# adc.net
KiCad netlist of a schematic drawn in Altium Designer
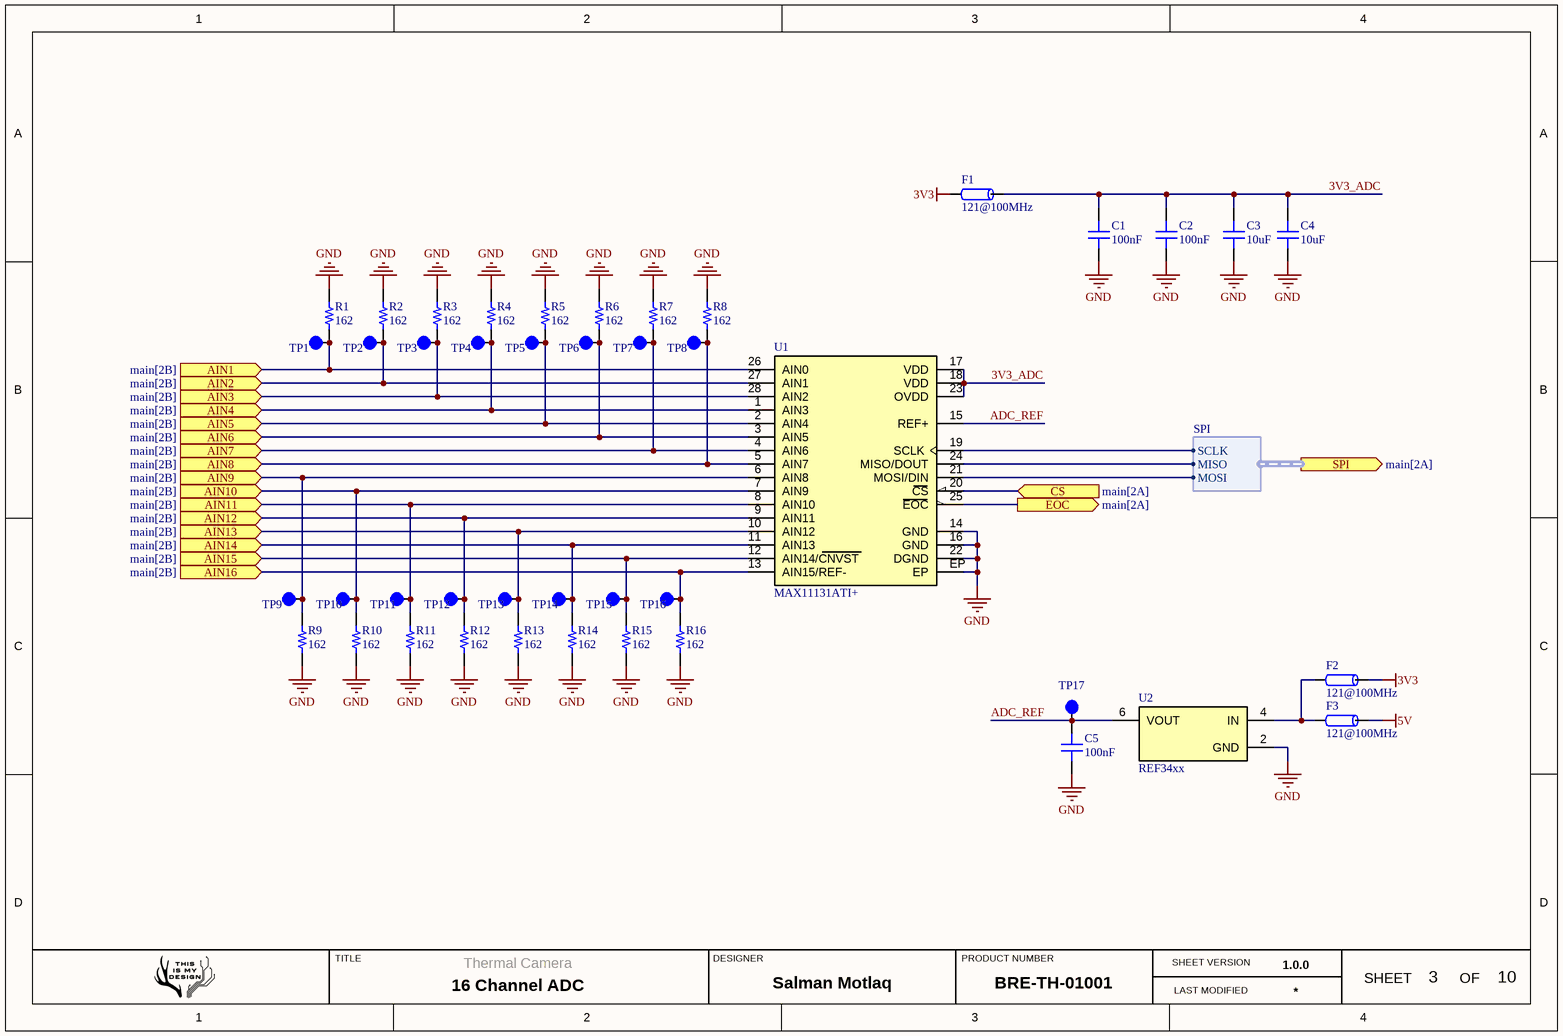
[diagram p0: adc.SchDoc]

(export (version "E")
  (design (tool "Eeschema 10.0.6"))
  (components
    (comp (ref "C1")
      (value "100nF")
      (footprint "CAP 0603_1608")
      (description "SMT Capacitor")
      (libsource (lib "Capacitor") (part "Cap 0603"))
    )
    (comp (ref "C2")
      (value "100nF")
      (footprint "CAP 0603_1608")
      (description "SMT Capacitor")
      (libsource (lib "Capacitor") (part "Cap 0603"))
    )
    (comp (ref "C3")
      (value "10uF")
      (footprint "CAP 0603_1608")
      (description "SMT Capacitor")
      (libsource (lib "Capacitor") (part "Cap 0603"))
    )
    (comp (ref "C4")
      (value "10uF")
      (footprint "CAP 0603_1608")
      (description "SMT Capacitor")
      (libsource (lib "Capacitor") (part "Cap 0603"))
    )
    (comp (ref "C5")
      (value "100nF")
      (footprint "CAP 0603_1608")
      (description "SMT Capacitor")
      (libsource (lib "Capacitor") (part "Cap 0603"))
    )
    (comp (ref "F1")
      (value "121@100MHz")
      (footprint "Ferrite-0805")
      (description "Ferrite Bead")
      (libsource (lib "Salman_lib") (part "Ferrite Bead"))
    )
    (comp (ref "F2")
      (value "121@100MHz")
      (footprint "Ferrite-0805")
      (description "Ferrite Bead")
      (libsource (lib "Salman_lib") (part "Ferrite Bead"))
    )
    (comp (ref "F3")
      (value "121@100MHz")
      (footprint "Ferrite-0805")
      (description "Ferrite Bead")
      (libsource (lib "Salman_lib") (part "Ferrite Bead"))
    )
    (comp (ref "R1")
      (value "162")
      (footprint "RES 0402_1005")
      (description "SMT Resistor")
      (libsource (lib "Resistor") (part "Res 0402"))
    )
    (comp (ref "R2")
      (value "162")
      (footprint "RES 0402_1005")
      (description "SMT Resistor")
      (libsource (lib "Resistor") (part "Res 0402"))
    )
    (comp (ref "R3")
      (value "162")
      (footprint "RES 0402_1005")
      (description "SMT Resistor")
      (libsource (lib "Resistor") (part "Res 0402"))
    )
    (comp (ref "R4")
      (value "162")
      (footprint "RES 0402_1005")
      (description "SMT Resistor")
      (libsource (lib "Resistor") (part "Res 0402"))
    )
    (comp (ref "R5")
      (value "162")
      (footprint "RES 0402_1005")
      (description "SMT Resistor")
      (libsource (lib "Resistor") (part "Res 0402"))
    )
    (comp (ref "R6")
      (value "162")
      (footprint "RES 0402_1005")
      (description "SMT Resistor")
      (libsource (lib "Resistor") (part "Res 0402"))
    )
    (comp (ref "R7")
      (value "162")
      (footprint "RES 0402_1005")
      (description "SMT Resistor")
      (libsource (lib "Resistor") (part "Res 0402"))
    )
    (comp (ref "R8")
      (value "162")
      (footprint "RES 0402_1005")
      (description "SMT Resistor")
      (libsource (lib "Resistor") (part "Res 0402"))
    )
    (comp (ref "R9")
      (value "162")
      (footprint "RES 0402_1005")
      (description "SMT Resistor")
      (libsource (lib "Resistor") (part "Res 0402"))
    )
    (comp (ref "R10")
      (value "162")
      (footprint "RES 0402_1005")
      (description "SMT Resistor")
      (libsource (lib "Resistor") (part "Res 0402"))
    )
    (comp (ref "R11")
      (value "162")
      (footprint "RES 0402_1005")
      (description "SMT Resistor")
      (libsource (lib "Resistor") (part "Res 0402"))
    )
    (comp (ref "R12")
      (value "162")
      (footprint "RES 0402_1005")
      (description "SMT Resistor")
      (libsource (lib "Resistor") (part "Res 0402"))
    )
    (comp (ref "R13")
      (value "162")
      (footprint "RES 0402_1005")
      (description "SMT Resistor")
      (libsource (lib "Resistor") (part "Res 0402"))
    )
    (comp (ref "R14")
      (value "162")
      (footprint "RES 0402_1005")
      (description "SMT Resistor")
      (libsource (lib "Resistor") (part "Res 0402"))
    )
    (comp (ref "R15")
      (value "162")
      (footprint "RES 0402_1005")
      (description "SMT Resistor")
      (libsource (lib "Resistor") (part "Res 0402"))
    )
    (comp (ref "R16")
      (value "162")
      (footprint "RES 0402_1005")
      (description "SMT Resistor")
      (libsource (lib "Resistor") (part "Res 0402"))
    )
    (comp (ref "TP1")
      (value "Test Point")
      (footprint "TEST_POINT_0R5")
      (description "PCB Test Point")
      (libsource (lib "BayanLib") (part "Test Point"))
    )
    (comp (ref "TP2")
      (value "Test Point")
      (footprint "TEST_POINT_0R5")
      (description "PCB Test Point")
      (libsource (lib "BayanLib") (part "Test Point"))
    )
    (comp (ref "TP3")
      (value "Test Point")
      (footprint "TEST_POINT_0R5")
      (description "PCB Test Point")
      (libsource (lib "BayanLib") (part "Test Point"))
    )
    (comp (ref "TP4")
      (value "Test Point")
      (footprint "TEST_POINT_0R5")
      (description "PCB Test Point")
      (libsource (lib "BayanLib") (part "Test Point"))
    )
    (comp (ref "TP5")
      (value "Test Point")
      (footprint "TEST_POINT_0R5")
      (description "PCB Test Point")
      (libsource (lib "BayanLib") (part "Test Point"))
    )
    (comp (ref "TP6")
      (value "Test Point")
      (footprint "TEST_POINT_0R5")
      (description "PCB Test Point")
      (libsource (lib "BayanLib") (part "Test Point"))
    )
    (comp (ref "TP7")
      (value "Test Point")
      (footprint "TEST_POINT_0R5")
      (description "PCB Test Point")
      (libsource (lib "BayanLib") (part "Test Point"))
    )
    (comp (ref "TP8")
      (value "Test Point")
      (footprint "TEST_POINT_0R5")
      (description "PCB Test Point")
      (libsource (lib "BayanLib") (part "Test Point"))
    )
    (comp (ref "TP9")
      (value "Test Point")
      (footprint "TEST_POINT_0R5")
      (description "PCB Test Point")
      (libsource (lib "BayanLib") (part "Test Point"))
    )
    (comp (ref "TP10")
      (value "Test Point")
      (footprint "TEST_POINT_0R5")
      (description "PCB Test Point")
      (libsource (lib "BayanLib") (part "Test Point"))
    )
    (comp (ref "TP11")
      (value "Test Point")
      (footprint "TEST_POINT_0R5")
      (description "PCB Test Point")
      (libsource (lib "BayanLib") (part "Test Point"))
    )
    (comp (ref "TP12")
      (value "Test Point")
      (footprint "TEST_POINT_0R5")
      (description "PCB Test Point")
      (libsource (lib "BayanLib") (part "Test Point"))
    )
    (comp (ref "TP13")
      (value "Test Point")
      (footprint "TEST_POINT_0R5")
      (description "PCB Test Point")
      (libsource (lib "BayanLib") (part "Test Point"))
    )
    (comp (ref "TP14")
      (value "Test Point")
      (footprint "TEST_POINT_0R5")
      (description "PCB Test Point")
      (libsource (lib "BayanLib") (part "Test Point"))
    )
    (comp (ref "TP15")
      (value "Test Point")
      (footprint "TEST_POINT_0R5")
      (description "PCB Test Point")
      (libsource (lib "BayanLib") (part "Test Point"))
    )
    (comp (ref "TP16")
      (value "Test Point")
      (footprint "TEST_POINT_0R5")
      (description "PCB Test Point")
      (libsource (lib "BayanLib") (part "Test Point"))
    )
    (comp (ref "TP17")
      (value "Test Point")
      (footprint "TEST_POINT_0R5")
      (description "PCB Test Point")
      (libsource (lib "BayanLib") (part "Test Point"))
    )
    (comp (ref "U1")
      (value "MAX11131ATI+")
      (footprint "TQFN-28")
      (libsource (lib "Salman_lib") (part "MAX11131"))
    )
    (comp (ref "U2")
      (value "REF34xx")
      (footprint "SOT23-6L")
      (description "Voltage References low-drift, low-power")
      (libsource (lib "Salman_lib") (part "REF34xx"))
    )
  )
  (nets
    (net (code "2") (name "/3V3_ADC") (class "Default")
      (node (ref "C1") (pin "2") (pinfunction "2_2") (pintype "passive"))
      (node (ref "C2") (pin "2") (pinfunction "2_2") (pintype "passive"))
      (node (ref "C3") (pin "2") (pinfunction "2_2") (pintype "passive"))
      (node (ref "C4") (pin "2") (pinfunction "2_2") (pintype "passive"))
      (node (ref "F1") (pin "2") (pinfunction "66_2") (pintype "passive"))
      (node (ref "U1") (pin "17") (pinfunction "VDD_17") (pintype "passive"))
      (node (ref "U1") (pin "18") (pinfunction "VDD_18") (pintype "passive"))
      (node (ref "U1") (pin "23") (pinfunction "OVDD_23") (pintype "passive"))
    )
    (net (code "3") (name "/ADC_REF") (class "Default")
      (node (ref "C5") (pin "2") (pinfunction "2_2") (pintype "passive"))
      (node (ref "TP17") (pin "0") (pinfunction "0_0") (pintype "passive"))
      (node (ref "U1") (pin "15") (pinfunction "REF+_15") (pintype "passive"))
      (node (ref "U2") (pin "6") (pinfunction "VOUT_6") (pintype "passive"))
    )
    (net (code "4") (name "/AIN1") (class "Default")
      (node (ref "R1") (pin "1") (pinfunction "1_1") (pintype "passive"))
      (node (ref "TP1") (pin "0") (pinfunction "0_0") (pintype "passive"))
      (node (ref "U1") (pin "26") (pinfunction "AIN0_26") (pintype "passive"))
    )
    (net (code "5") (name "/AIN2") (class "Default")
      (node (ref "R2") (pin "1") (pinfunction "1_1") (pintype "passive"))
      (node (ref "TP2") (pin "0") (pinfunction "0_0") (pintype "passive"))
      (node (ref "U1") (pin "27") (pinfunction "AIN1_27") (pintype "passive"))
    )
    (net (code "6") (name "/AIN3") (class "Default")
      (node (ref "R3") (pin "1") (pinfunction "1_1") (pintype "passive"))
      (node (ref "TP3") (pin "0") (pinfunction "0_0") (pintype "passive"))
      (node (ref "U1") (pin "28") (pinfunction "AIN2_28") (pintype "passive"))
    )
    (net (code "7") (name "/AIN4") (class "Default")
      (node (ref "R4") (pin "1") (pinfunction "1_1") (pintype "passive"))
      (node (ref "TP4") (pin "0") (pinfunction "0_0") (pintype "passive"))
      (node (ref "U1") (pin "1") (pinfunction "AIN3_1") (pintype "passive"))
    )
    (net (code "8") (name "/AIN5") (class "Default")
      (node (ref "R5") (pin "1") (pinfunction "1_1") (pintype "passive"))
      (node (ref "TP5") (pin "0") (pinfunction "0_0") (pintype "passive"))
      (node (ref "U1") (pin "2") (pinfunction "AIN4_2") (pintype "passive"))
    )
    (net (code "9") (name "/AIN6") (class "Default")
      (node (ref "R6") (pin "1") (pinfunction "1_1") (pintype "passive"))
      (node (ref "TP6") (pin "0") (pinfunction "0_0") (pintype "passive"))
      (node (ref "U1") (pin "3") (pinfunction "AIN5_3") (pintype "passive"))
    )
    (net (code "10") (name "/AIN7") (class "Default")
      (node (ref "R7") (pin "1") (pinfunction "1_1") (pintype "passive"))
      (node (ref "TP7") (pin "0") (pinfunction "0_0") (pintype "passive"))
      (node (ref "U1") (pin "4") (pinfunction "AIN6_4") (pintype "passive"))
    )
    (net (code "11") (name "/AIN8") (class "Default")
      (node (ref "R8") (pin "1") (pinfunction "1_1") (pintype "passive"))
      (node (ref "TP8") (pin "0") (pinfunction "0_0") (pintype "passive"))
      (node (ref "U1") (pin "5") (pinfunction "AIN7_5") (pintype "passive"))
    )
    (net (code "12") (name "/AIN9") (class "Default")
      (node (ref "R9") (pin "2") (pinfunction "2_2") (pintype "passive"))
      (node (ref "TP9") (pin "0") (pinfunction "0_0") (pintype "passive"))
      (node (ref "U1") (pin "6") (pinfunction "AIN8_6") (pintype "passive"))
    )
    (net (code "13") (name "/AIN10") (class "Default")
      (node (ref "R10") (pin "2") (pinfunction "2_2") (pintype "passive"))
      (node (ref "TP10") (pin "0") (pinfunction "0_0") (pintype "passive"))
      (node (ref "U1") (pin "7") (pinfunction "AIN9_7") (pintype "passive"))
    )
    (net (code "14") (name "/AIN11") (class "Default")
      (node (ref "R11") (pin "2") (pinfunction "2_2") (pintype "passive"))
      (node (ref "TP11") (pin "0") (pinfunction "0_0") (pintype "passive"))
      (node (ref "U1") (pin "8") (pinfunction "AIN10_8") (pintype "passive"))
    )
    (net (code "15") (name "/AIN12") (class "Default")
      (node (ref "R12") (pin "2") (pinfunction "2_2") (pintype "passive"))
      (node (ref "TP12") (pin "0") (pinfunction "0_0") (pintype "passive"))
      (node (ref "U1") (pin "9") (pinfunction "AIN11_9") (pintype "passive"))
    )
    (net (code "16") (name "/AIN13") (class "Default")
      (node (ref "R13") (pin "2") (pinfunction "2_2") (pintype "passive"))
      (node (ref "TP13") (pin "0") (pinfunction "0_0") (pintype "passive"))
      (node (ref "U1") (pin "10") (pinfunction "AIN12_10") (pintype "passive"))
    )
    (net (code "17") (name "/AIN14") (class "Default")
      (node (ref "R14") (pin "2") (pinfunction "2_2") (pintype "passive"))
      (node (ref "TP14") (pin "0") (pinfunction "0_0") (pintype "passive"))
      (node (ref "U1") (pin "11") (pinfunction "AIN13_11") (pintype "passive"))
    )
    (net (code "18") (name "/AIN15") (class "Default")
      (node (ref "R15") (pin "2") (pinfunction "2_2") (pintype "passive"))
      (node (ref "TP15") (pin "0") (pinfunction "0_0") (pintype "passive"))
      (node (ref "U1") (pin "12") (pinfunction "AIN14/CNVST_12") (pintype "passive"))
    )
    (net (code "19") (name "/AIN16") (class "Default")
      (node (ref "R16") (pin "2") (pinfunction "2_2") (pintype "passive"))
      (node (ref "TP16") (pin "0") (pinfunction "0_0") (pintype "passive"))
      (node (ref "U1") (pin "13") (pinfunction "AIN15/REF-_13") (pintype "passive"))
    )
    (net (code "20") (name "/CS") (class "Default")
      (node (ref "U1") (pin "20") (pinfunction "CS_20") (pintype "passive"))
    )
    (net (code "21") (name "/EOC") (class "Default")
      (node (ref "U1") (pin "25") (pinfunction "EOC_25") (pintype "passive"))
    )
    (net (code "22") (name "/MISO") (class "Default")
      (node (ref "U1") (pin "24") (pinfunction "MISO/DOUT_24") (pintype "passive"))
    )
    (net (code "23") (name "/MOSI") (class "Default")
      (node (ref "U1") (pin "21") (pinfunction "MOSI/DIN_21") (pintype "passive"))
    )
    (net (code "24") (name "/SCLK") (class "Default")
      (node (ref "U1") (pin "19") (pinfunction "SCLK_19") (pintype "passive"))
    )
    (net (code "26") (name "3V3") (class "Default")
      (node (ref "F1") (pin "1") (pinfunction "67_1") (pintype "passive"))
      (node (ref "F2") (pin "2") (pinfunction "66_2") (pintype "passive"))
    )
    (net (code "27") (name "5V") (class "Default")
      (node (ref "F3") (pin "2") (pinfunction "66_2") (pintype "passive"))
    )
    (net (code "28") (name "GND") (class "Default")
      (node (ref "C1") (pin "1") (pinfunction "1_1") (pintype "passive"))
      (node (ref "C2") (pin "1") (pinfunction "1_1") (pintype "passive"))
      (node (ref "C3") (pin "1") (pinfunction "1_1") (pintype "passive"))
      (node (ref "C4") (pin "1") (pinfunction "1_1") (pintype "passive"))
      (node (ref "C5") (pin "1") (pinfunction "1_1") (pintype "passive"))
      (node (ref "R1") (pin "2") (pinfunction "2_2") (pintype "passive"))
      (node (ref "R10") (pin "1") (pinfunction "1_1") (pintype "passive"))
      (node (ref "R11") (pin "1") (pinfunction "1_1") (pintype "passive"))
      (node (ref "R12") (pin "1") (pinfunction "1_1") (pintype "passive"))
      (node (ref "R13") (pin "1") (pinfunction "1_1") (pintype "passive"))
      (node (ref "R14") (pin "1") (pinfunction "1_1") (pintype "passive"))
      (node (ref "R15") (pin "1") (pinfunction "1_1") (pintype "passive"))
      (node (ref "R16") (pin "1") (pinfunction "1_1") (pintype "passive"))
      (node (ref "R2") (pin "2") (pinfunction "2_2") (pintype "passive"))
      (node (ref "R3") (pin "2") (pinfunction "2_2") (pintype "passive"))
      (node (ref "R4") (pin "2") (pinfunction "2_2") (pintype "passive"))
      (node (ref "R5") (pin "2") (pinfunction "2_2") (pintype "passive"))
      (node (ref "R6") (pin "2") (pinfunction "2_2") (pintype "passive"))
      (node (ref "R7") (pin "2") (pinfunction "2_2") (pintype "passive"))
      (node (ref "R8") (pin "2") (pinfunction "2_2") (pintype "passive"))
      (node (ref "R9") (pin "1") (pinfunction "1_1") (pintype "passive"))
      (node (ref "U1") (pin "14") (pinfunction "GND_14") (pintype "passive"))
      (node (ref "U1") (pin "16") (pinfunction "GND_16") (pintype "passive"))
      (node (ref "U1") (pin "22") (pinfunction "DGND_22") (pintype "passive"))
      (node (ref "U1") (pin "EP") (pinfunction "EP_EP") (pintype "passive"))
      (node (ref "U2") (pin "2") (pinfunction "GND_2") (pintype "passive"))
    )
    (net (code "29") (name "Net-(F2-67)") (class "Default")
      (node (ref "F2") (pin "1") (pinfunction "67_1") (pintype "passive"))
      (node (ref "F3") (pin "1") (pinfunction "67_1") (pintype "passive"))
      (node (ref "U2") (pin "4") (pinfunction "IN_4") (pintype "passive"))
    )
  )
)
